# op-amp.net
KiCad netlist of a schematic drawn in EAGLE
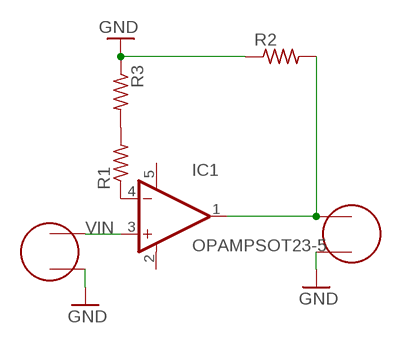
[diagram p0: schematic, sheet 1]

(export (version "E")
  (design (tool "Eeschema 10.0.6"))
  (components
    (comp (ref "IC1")
      (value "OPAMPSOT23-5")
      (footprint "eagle-import:SOT23-5")
      (libsource (lib "eagle-import") (part "OPAMPSOT23-5"))
    )
    (comp (ref "R1")
      (value "RES-US1206FAB")
      (footprint "eagle-import:R1206FAB")
      (libsource (lib "eagle-import") (part "RES-US1206FAB"))
    )
    (comp (ref "R2")
      (value "RES-US1206FAB")
      (footprint "eagle-import:R1206FAB")
      (libsource (lib "eagle-import") (part "RES-US1206FAB"))
    )
    (comp (ref "R3")
      (value "RES-US1206FAB")
      (footprint "eagle-import:R1206FAB")
      (libsource (lib "eagle-import") (part "RES-US1206FAB"))
    )
    (comp (ref "U$3")
      (value "PINHD-2X1-SMD")
      (footprint "eagle-import:2X01SMD")
      (libsource (lib "eagle-import") (part "PINHD-2X1-SMD"))
    )
    (comp (ref "U$4")
      (value "PINHD-2X1-SMD")
      (footprint "eagle-import:2X01SMD")
      (libsource (lib "eagle-import") (part "PINHD-2X1-SMD"))
    )
  )
  (nets
    (net (code "1") (name "/V+") (class "Default")
      (node (ref "IC1") (pin "5") (pinfunction "V+_5") (pintype "power_in"))
    )
    (net (code "2") (name "/V-") (class "Default")
      (node (ref "IC1") (pin "2") (pinfunction "V-_2") (pintype "power_in"))
    )
    (net (code "3") (name "/VIN") (class "Default")
      (node (ref "IC1") (pin "3") (pinfunction "+IN_3") (pintype "input"))
      (node (ref "U$4") (pin "4") (pinfunction "P$2_4") (pintype "bidirectional"))
    )
    (net (code "4") (name "GND") (class "Default")
      (node (ref "R2") (pin "1") (pinfunction "1_1") (pintype "passive"))
      (node (ref "R3") (pin "1") (pinfunction "1_1") (pintype "passive"))
      (node (ref "U$3") (pin "4") (pinfunction "P$2_4") (pintype "bidirectional"))
      (node (ref "U$4") (pin "3") (pinfunction "P$1_3") (pintype "bidirectional"))
    )
    (net (code "5") (name "Net-(IC1--IN)") (class "Default")
      (node (ref "IC1") (pin "4") (pinfunction "-IN_4") (pintype "input"))
      (node (ref "R1") (pin "1") (pinfunction "1_1") (pintype "passive"))
    )
    (net (code "6") (name "Net-(IC1-OUT)") (class "Default")
      (node (ref "IC1") (pin "1") (pinfunction "OUT_1") (pintype "output"))
      (node (ref "R2") (pin "2") (pinfunction "2_2") (pintype "passive"))
      (node (ref "U$3") (pin "3") (pinfunction "P$1_3") (pintype "bidirectional"))
    )
    (net (code "7") (name "Net-(R1-Pad2)") (class "Default")
      (node (ref "R1") (pin "2") (pinfunction "2_2") (pintype "passive"))
      (node (ref "R3") (pin "2") (pinfunction "2_2") (pintype "passive"))
    )
  )
)
